# RGB_LED.net
KiCad netlist of a schematic drawn in EAGLE
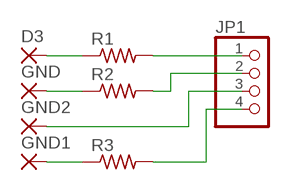
[diagram p0: schematic, sheet 1]

(export (version "E")
  (design (tool "Eeschema 10.0.6"))
  (components
    (comp (ref "D3")
      (value "2,15/1,0")
      (footprint "eagle-import:2,15_1,0")
      (libsource (lib "eagle-import") (part "2,15/1,0"))
    )
    (comp (ref "GND")
      (value "2,15/1,0")
      (footprint "eagle-import:2,15_1,0")
      (libsource (lib "eagle-import") (part "2,15/1,0"))
    )
    (comp (ref "GND1")
      (value "2,15/1,0")
      (footprint "eagle-import:2,15_1,0")
      (libsource (lib "eagle-import") (part "2,15/1,0"))
    )
    (comp (ref "GND2")
      (value "2,15/1,0")
      (footprint "eagle-import:2,15_1,0")
      (libsource (lib "eagle-import") (part "2,15/1,0"))
    )
    (comp (ref "JP1")
      (value "PINHD-1X4")
      (footprint "eagle-import:1X04")
      (libsource (lib "eagle-import") (part "PINHD-1X4"))
    )
    (comp (ref "R1")
      (value "R-US_R1206")
      (footprint "eagle-import:R1206")
      (libsource (lib "eagle-import") (part "R-US_R1206"))
    )
    (comp (ref "R2")
      (value "R-US_R1206")
      (footprint "eagle-import:R1206")
      (libsource (lib "eagle-import") (part "R-US_R1206"))
    )
    (comp (ref "R3")
      (value "R-US_R1206")
      (footprint "eagle-import:R1206")
      (libsource (lib "eagle-import") (part "R-US_R1206"))
    )
  )
  (nets
    (net (code "1") (name "Net-(D3-P)") (class "Default")
      (node (ref "D3") (pin "1") (pinfunction "P_1") (pintype "passive"))
      (node (ref "R1") (pin "1") (pinfunction "1_1") (pintype "passive"))
    )
    (net (code "2") (name "Net-(GND-P)") (class "Default")
      (node (ref "GND") (pin "1") (pinfunction "P_1") (pintype "passive"))
      (node (ref "R2") (pin "1") (pinfunction "1_1") (pintype "passive"))
    )
    (net (code "3") (name "Net-(GND1-P)") (class "Default")
      (node (ref "GND1") (pin "1") (pinfunction "P_1") (pintype "passive"))
      (node (ref "R3") (pin "1") (pinfunction "1_1") (pintype "passive"))
    )
    (net (code "4") (name "Net-(GND2-P)") (class "Default")
      (node (ref "GND2") (pin "1") (pinfunction "P_1") (pintype "passive"))
      (node (ref "JP1") (pin "3") (pinfunction "3_3") (pintype "passive"))
    )
    (net (code "5") (name "Net-(JP1-Pad1)") (class "Default")
      (node (ref "JP1") (pin "1") (pinfunction "1_1") (pintype "passive"))
      (node (ref "R1") (pin "2") (pinfunction "2_2") (pintype "passive"))
    )
    (net (code "6") (name "Net-(JP1-Pad2)") (class "Default")
      (node (ref "JP1") (pin "2") (pinfunction "2_2") (pintype "passive"))
      (node (ref "R2") (pin "2") (pinfunction "2_2") (pintype "passive"))
    )
    (net (code "7") (name "Net-(JP1-Pad4)") (class "Default")
      (node (ref "JP1") (pin "4") (pinfunction "4_4") (pintype "passive"))
      (node (ref "R3") (pin "2") (pinfunction "2_2") (pintype "passive"))
    )
  )
)
